# USB.net
KiCad netlist of a schematic drawn in Altium Designer
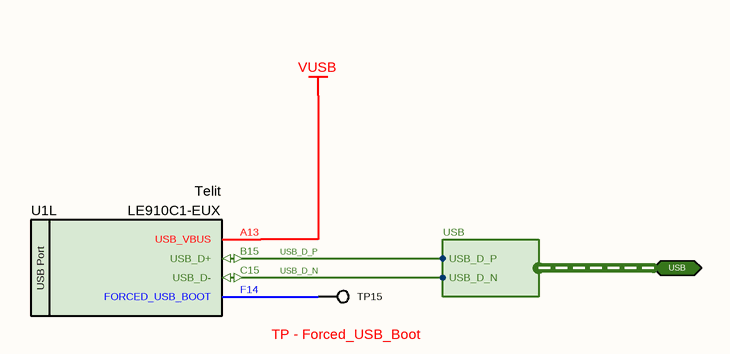
[diagram p0: USB.SchDoc]

(export (version "E")
  (design (tool "Eeschema 10.0.6"))
  (components
    (comp (ref "TP15")
      (value "TP - Forced_USB_Boot")
      (footprint "TP")
      (description "Test Point")
      (libsource (lib "Akkoyun") (part "PCB - Test Point"))
    )
    (comp (ref "U1")
      (value "LE910C1-EUX LTE GSM Module")
      (footprint "LE910 GSM Modem")
      (description "Telit LE910C1-EUX LTE/2G GSM Module")
      (fields
        (field (name "MANUFACTURER PART NUMBER") "LE910C1-EUX")
        (field (name "MANUFACTURER NAME") "Telit")
      )
      (libsource (lib "Akkoyun") (part "IC - LE910C1-EUX"))
    )
  )
  (nets
    (net (code "2") (name "/USB_D_N") (class "Default")
      (node (ref "U1") (pin "C15") (pinfunction "USB_D-_C15") (pintype "bidirectional"))
    )
    (net (code "3") (name "/USB_D_P") (class "Default")
      (node (ref "U1") (pin "B15") (pinfunction "USB_D+_B15") (pintype "bidirectional"))
    )
    (net (code "5") (name "Net-(U1L-FORCED_USB_BOOT)") (class "Default")
      (node (ref "TP15") (pin "1") (pinfunction "1_1") (pintype "passive"))
      (node (ref "U1") (pin "F14") (pinfunction "FORCED_USB_BOOT_F14") (pintype "passive"))
    )
    (net (code "6") (name "VUSB") (class "Default")
      (node (ref "U1") (pin "A13") (pinfunction "USB_VBUS_A13") (pintype "power_in"))
    )
  )
)
